# DRV8323RH.net
KiCad netlist of a schematic drawn in EAGLE
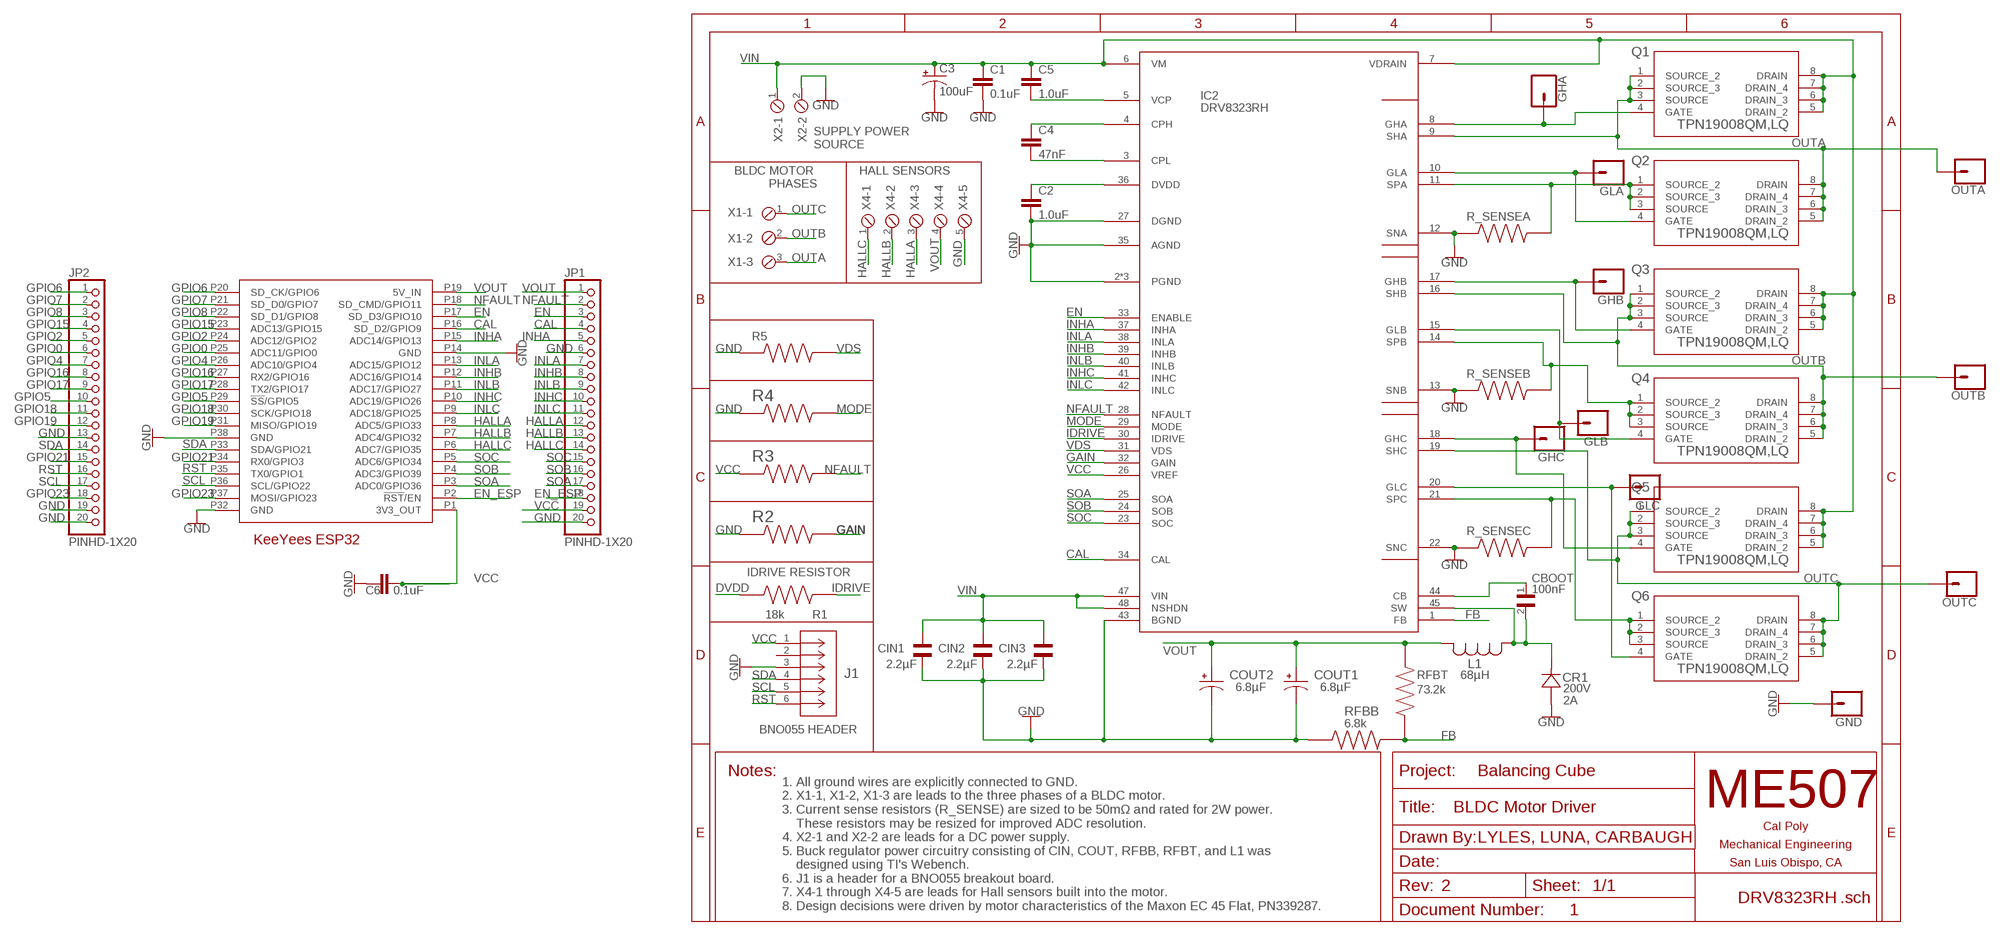
[diagram p0: schematic, sheet 1]

(export (version "E")
  (design (tool "Eeschema 10.0.6"))
  (components
    (comp (ref "C1")
      (value "0.1uF")
      (footprint "eagle-import:0603")
      (libsource (lib "eagle-import") (part "0.1UF-0603-50V-10%-X7R-WE"))
    )
    (comp (ref "C2")
      (value "1.0uF")
      (footprint "eagle-import:0805")
      (libsource (lib "eagle-import") (part "1.0UF-0805-25V-10%"))
    )
    (comp (ref "C3")
      (value "100uF")
      (footprint "eagle-import:CPOL-RADIAL-2.5MM-6.5MM")
      (libsource (lib "eagle-import") (part "100UF-POLAR-RADIAL-2.5MM-25V-20%"))
    )
    (comp (ref "C4")
      (value "47nF")
      (footprint "eagle-import:0603")
      (libsource (lib "eagle-import") (part "47NF-0603-25V-5%"))
    )
    (comp (ref "C5")
      (value "1.0uF")
      (footprint "eagle-import:0805")
      (libsource (lib "eagle-import") (part "1.0UF-0805-25V-10%"))
    )
    (comp (ref "C6")
      (value "0.1uF")
      (footprint "eagle-import:0603")
      (libsource (lib "eagle-import") (part "0.1UF-0603-50V-10%-X7R-WE"))
    )
    (comp (ref "CBOOT")
      (value "C2012X7R2A104K125AA")
      (footprint "eagle-import:CAPC2012X145N")
      (fields (field (name "MF") "TDK") (field (name "VAL") "100nF"))
      (libsource (lib "eagle-import") (part "C2012X7R2A104K125AA"))
    )
    (comp (ref "CIN1")
      (value "C3225X7R2A225K230AB")
      (footprint "eagle-import:CAP_C3225X7R2A225K230AB")
      (fields (field (name "MF") "TDK") (field (name "VAL") "2.2µF"))
      (libsource (lib "eagle-import") (part "C3225X7R2A225K230AB"))
    )
    (comp (ref "CIN2")
      (value "C3225X7R2A225K230AB")
      (footprint "eagle-import:CAP_C3225X7R2A225K230AB")
      (fields (field (name "MF") "TDK") (field (name "VAL") "2.2µF"))
      (libsource (lib "eagle-import") (part "C3225X7R2A225K230AB"))
    )
    (comp (ref "CIN3")
      (value "C3225X7R2A225K230AB")
      (footprint "eagle-import:CAP_C3225X7R2A225K230AB")
      (fields (field (name "MF") "TDK") (field (name "VAL") "2.2µF"))
      (libsource (lib "eagle-import") (part "C3225X7R2A225K230AB"))
    )
    (comp (ref "COUT1")
      (value "TPSD685K050R0600")
      (footprint "eagle-import:CAPPM7343X310N")
      (fields
        (field (name "DIGI-KEY_PART_NUMBER") "478-4121-2-ND")
        (field (name "MF") "AVX")
        (field (name "VAL") "6.8µF")
      )
      (libsource (lib "eagle-import") (part "TPSD685K050R0600"))
    )
    (comp (ref "COUT2")
      (value "TPSD685K050R0600")
      (footprint "eagle-import:CAPPM7343X310N")
      (fields
        (field (name "DIGI-KEY_PART_NUMBER") "478-4121-2-ND")
        (field (name "MF") "AVX")
        (field (name "VAL") "6.8µF")
      )
      (libsource (lib "eagle-import") (part "TPSD685K050R0600"))
    )
    (comp (ref "CR1")
      (value "SK220ATRDIODE_SK220ATR_SMC-L")
      (footprint "eagle-import:DIODE_SK220ATR_SMC-L")
      (fields
        (field (name "MANUFACTURER_PART_NUMBER") "SK220ATR")
        (field (name "CURR") "2A")
        (field (name "VOLT") "200V")
        (field (name "COPYRIGHT") "Copyright (C) 2022 Ultra Librarian. All rights reserved.")
      )
      (libsource (lib "eagle-import") (part "SK220ATRDIODE_SK220ATR_SMC-L"))
    )
    (comp (ref "GHA")
      (value "CONN_01_1MM")
      (footprint "eagle-import:1X01_1MM_NO_SILK")
      (libsource (lib "eagle-import") (part "CONN_01_1MM"))
    )
    (comp (ref "GHB")
      (value "CONN_01_1MM")
      (footprint "eagle-import:1X01_1MM_NO_SILK")
      (libsource (lib "eagle-import") (part "CONN_01_1MM"))
    )
    (comp (ref "GHC")
      (value "CONN_01_1MM")
      (footprint "eagle-import:1X01_1MM_NO_SILK")
      (libsource (lib "eagle-import") (part "CONN_01_1MM"))
    )
    (comp (ref "GLA")
      (value "CONN_01_1MM")
      (footprint "eagle-import:1X01_1MM_NO_SILK")
      (libsource (lib "eagle-import") (part "CONN_01_1MM"))
    )
    (comp (ref "GLB")
      (value "CONN_01_1MM")
      (footprint "eagle-import:1X01_1MM_NO_SILK")
      (libsource (lib "eagle-import") (part "CONN_01_1MM"))
    )
    (comp (ref "GLC")
      (value "CONN_01_1MM")
      (footprint "eagle-import:1X01_1MM_NO_SILK")
      (libsource (lib "eagle-import") (part "CONN_01_1MM"))
    )
    (comp (ref "GND")
      (value "CONN_01_1MM")
      (footprint "eagle-import:1X01_1MM_NO_SILK")
      (libsource (lib "eagle-import") (part "CONN_01_1MM"))
    )
    (comp (ref "IC2")
      (value "DRV8323RH")
      (footprint "eagle-import:QFN50P700X700X100-49T515")
      (libsource (lib "eagle-import") (part "DRV8323RH"))
    )
    (comp (ref "J1")
      (value "PPTC061LFBN-RCCONN6_061LFBN-RC_SUL")
      (footprint "eagle-import:CONN6_061LFBN-RC_SUL")
      (fields
        (field (name "MANUFACTURER_PART_NUMBER") "PPTC061LFBN-RC")
        (field (name "COPYRIGHT") "Copyright (C) 2022 Ultra Librarian. All rights reserved.")
      )
      (libsource (lib "eagle-import") (part "PPTC061LFBN-RCCONN6_061LFBN-RC_SUL"))
    )
    (comp (ref "JP1")
      (value "PINHD-1X20")
      (footprint "eagle-import:1X20")
      (libsource (lib "eagle-import") (part "PINHD-1X20"))
    )
    (comp (ref "JP2")
      (value "PINHD-1X20")
      (footprint "eagle-import:1X20")
      (libsource (lib "eagle-import") (part "PINHD-1X20"))
    )
    (comp (ref "L1")
      (value "SRR1210-680MIND_BOURNS_SRR1210")
      (footprint "eagle-import:IND_BOURNS_SRR1210")
      (fields
        (field (name "MANUFACTURER_PART_NUMBER") "SRR1210-680M")
        (field (name "VAL") "68µH")
        (field (name "COPYRIGHT") "Copyright (C) 2022 Ultra Librarian. All rights reserved.")
      )
      (libsource (lib "eagle-import") (part "SRR1210-680MIND_BOURNS_SRR1210"))
    )
    (comp (ref "OUTA")
      (value "CONN_01_1MM")
      (footprint "eagle-import:1X01_1MM_NO_SILK")
      (libsource (lib "eagle-import") (part "CONN_01_1MM"))
    )
    (comp (ref "OUTB")
      (value "CONN_01_1MM")
      (footprint "eagle-import:1X01_1MM_NO_SILK")
      (libsource (lib "eagle-import") (part "CONN_01_1MM"))
    )
    (comp (ref "OUTC")
      (value "CONN_01_1MM")
      (footprint "eagle-import:1X01_1MM_NO_SILK")
      (libsource (lib "eagle-import") (part "CONN_01_1MM"))
    )
    (comp (ref "Q1")
      (value "TPN19008QM,LQ")
      (footprint "eagle-import:TSON_ADVANCE_TOS")
      (fields (field (name "COPYRIGHT") "Copyright (C) 2022 Ultra Librarian. All rights reserved."))
      (libsource (lib "eagle-import") (part "TPN19008QM,LQ"))
    )
    (comp (ref "Q2")
      (value "TPN19008QM,LQ")
      (footprint "eagle-import:TSON_ADVANCE_TOS")
      (fields (field (name "COPYRIGHT") "Copyright (C) 2022 Ultra Librarian. All rights reserved."))
      (libsource (lib "eagle-import") (part "TPN19008QM,LQ"))
    )
    (comp (ref "Q3")
      (value "TPN19008QM,LQ")
      (footprint "eagle-import:TSON_ADVANCE_TOS")
      (fields (field (name "COPYRIGHT") "Copyright (C) 2022 Ultra Librarian. All rights reserved."))
      (libsource (lib "eagle-import") (part "TPN19008QM,LQ"))
    )
    (comp (ref "Q4")
      (value "TPN19008QM,LQ")
      (footprint "eagle-import:TSON_ADVANCE_TOS")
      (fields (field (name "COPYRIGHT") "Copyright (C) 2022 Ultra Librarian. All rights reserved."))
      (libsource (lib "eagle-import") (part "TPN19008QM,LQ"))
    )
    (comp (ref "Q5")
      (value "TPN19008QM,LQ")
      (footprint "eagle-import:TSON_ADVANCE_TOS")
      (fields (field (name "COPYRIGHT") "Copyright (C) 2022 Ultra Librarian. All rights reserved."))
      (libsource (lib "eagle-import") (part "TPN19008QM,LQ"))
    )
    (comp (ref "Q6")
      (value "TPN19008QM,LQ")
      (footprint "eagle-import:TSON_ADVANCE_TOS")
      (fields (field (name "COPYRIGHT") "Copyright (C) 2022 Ultra Librarian. All rights reserved."))
      (libsource (lib "eagle-import") (part "TPN19008QM,LQ"))
    )
    (comp (ref "R1")
      (value "ERJP06J183V")
      (footprint "eagle-import:RES_ERJP06J183V")
      (fields
        (field (name "DIGI-KEY_PART_NUMBER") "P18KADTR-ND")
        (field (name "MF") "Panasonic")
        (field (name "NAM") "R1")
        (field (name "VAL") "18k")
      )
      (libsource (lib "eagle-import") (part "ERJP06J183V"))
    )
    (comp (ref "R2")
      (value "RMCF0805JT750K")
      (footprint "eagle-import:RESC2012X65N")
      (fields
        (field (name "DIGI-KEY_PART_NUMBER") "RMCF0805JT750KTR-ND")
        (field (name "MF") "Stackpole Electronics Inc")
      )
      (libsource (lib "eagle-import") (part "RMCF0805JT750K"))
    )
    (comp (ref "R3")
      (value "RC0805JR-0710KP")
      (footprint "eagle-import:RESC2012X60N")
      (fields (field (name "DIGI-KEY_PART_NUMBER") "YAG1329TR-ND") (field (name "MF") "Yageo"))
      (libsource (lib "eagle-import") (part "RC0805JR-0710KP"))
    )
    (comp (ref "R4")
      (value "RNCF0805DTE47K0")
      (footprint "eagle-import:RESC2012X65N")
      (fields
        (field (name "DIGI-KEY_PART_NUMBER") "738-RNCF0805DTE47K0TR-ND")
        (field (name "MF") "Stackpole Electronics Inc")
      )
      (libsource (lib "eagle-import") (part "RNCF0805DTE47K0"))
    )
    (comp (ref "R5")
      (value "ERJP06J183V")
      (footprint "eagle-import:RES_ERJP06J183V")
      (fields (field (name "DIGI-KEY_PART_NUMBER") "P18KADTR-ND") (field (name "MF") "Panasonic"))
      (libsource (lib "eagle-import") (part "ERJP06J183V"))
    )
    (comp (ref "RFBB")
      (value "RC1206FR-076K8L")
      (footprint "eagle-import:RESC3116X65N")
      (fields
        (field (name "DIGI-KEY_PART_NUMBER") "311-6.80KFRTR-ND")
        (field (name "MF") "Yageo")
        (field (name "VAL") "6.8k")
      )
      (libsource (lib "eagle-import") (part "RC1206FR-076K8L"))
    )
    (comp (ref "RFBT")
      (value "RR1220P-7322-D-M")
      (footprint "eagle-import:RESC2012X50N")
      (fields
        (field (name "DIGI-KEY_PART_NUMBER") "RR12P73.2KDTR-ND")
        (field (name "MF") "Susumu")
        (field (name "VAL") "73.2k")
      )
      (libsource (lib "eagle-import") (part "RR1220P-7322-D-M"))
    )
    (comp (ref "R_SENSEA")
      (value "CRM2512-FX-R300ELF")
      (footprint "eagle-import:RESC6331X80N")
      (fields
        (field (name "DIGI-KEY_PART_NUMBER") "CRM2512-FX-R300ELFTR-ND")
        (field (name "MF") "Bourns")
        (field (name "VAL") "0.305")
      )
      (libsource (lib "eagle-import") (part "CRM2512-FX-R300ELF"))
    )
    (comp (ref "R_SENSEB")
      (value "CRM2512-FX-R300ELF")
      (footprint "eagle-import:RESC6331X80N")
      (fields (field (name "DIGI-KEY_PART_NUMBER") "CRM2512-FX-R300ELFTR-ND") (field (name "MF") "Bourns"))
      (libsource (lib "eagle-import") (part "CRM2512-FX-R300ELF"))
    )
    (comp (ref "R_SENSEC")
      (value "CRM2512-FX-R300ELF")
      (footprint "eagle-import:RESC6331X80N")
      (fields (field (name "DIGI-KEY_PART_NUMBER") "CRM2512-FX-R300ELFTR-ND") (field (name "MF") "Bourns"))
      (libsource (lib "eagle-import") (part "CRM2512-FX-R300ELF"))
    )
    (comp (ref "U$1")
      (value "KEEYEES_ESP32EXT")
      (footprint "eagle-import:KEEYEES_ESP32_EXTENDED")
      (libsource (lib "eagle-import") (part "KEEYEES_ESP32EXT"))
    )
    (comp (ref "X1")
      (value "SCREWTERM_3P_508")
      (footprint "eagle-import:3POL508")
      (libsource (lib "eagle-import") (part "SCREWTERM_3P_508"))
    )
    (comp (ref "X2")
      (value "SCREWTERM_2P_508")
      (footprint "eagle-import:2POL508")
      (libsource (lib "eagle-import") (part "SCREWTERM_2P_508"))
    )
    (comp (ref "X4")
      (value "SCREWTERM_5P_508")
      (footprint "eagle-import:5POL508")
      (libsource (lib "eagle-import") (part "SCREWTERM_5P_508"))
    )
  )
  (nets
    (net (code "1") (name "/CAL") (class "Default")
      (node (ref "IC2") (pin "34") (pinfunction "CAL_34") (pintype "bidirectional"))
      (node (ref "JP1") (pin "4") (pinfunction "4_4") (pintype "passive"))
      (node (ref "U$1") (pin "P16") (pinfunction "SD_D2/GPIO9_P16") (pintype "bidirectional"))
    )
    (net (code "2") (name "/DVDD") (class "Default")
      (node (ref "C2") (pin "1") (pinfunction "1_1") (pintype "passive"))
      (node (ref "IC2") (pin "36") (pinfunction "DVDD_36") (pintype "bidirectional"))
      (node (ref "R1") (pin "1") (pinfunction "1_1") (pintype "passive"))
    )
    (net (code "3") (name "/EN") (class "Default")
      (node (ref "IC2") (pin "33") (pinfunction "ENABLE_33") (pintype "bidirectional"))
      (node (ref "JP1") (pin "3") (pinfunction "3_3") (pintype "passive"))
      (node (ref "U$1") (pin "P17") (pinfunction "SD_D3/GPIO10_P17") (pintype "bidirectional"))
    )
    (net (code "4") (name "/EN_ESP") (class "Default")
      (node (ref "JP1") (pin "18") (pinfunction "18_18") (pintype "passive"))
      (node (ref "U$1") (pin "P2") (pinfunction "~{RST}/EN_P2") (pintype "input"))
    )
    (net (code "5") (name "/FB") (class "Default")
      (node (ref "IC2") (pin "1") (pinfunction "FB_1") (pintype "bidirectional"))
      (node (ref "RFBB") (pin "2") (pinfunction "2_2") (pintype "passive"))
      (node (ref "RFBT") (pin "1") (pinfunction "1_1") (pintype "passive"))
    )
    (net (code "6") (name "/GAIN") (class "Default")
      (node (ref "IC2") (pin "32") (pinfunction "GAIN_32") (pintype "bidirectional"))
      (node (ref "R2") (pin "2") (pinfunction "2_2") (pintype "passive"))
    )
    (net (code "7") (name "/GPIO0") (class "Default")
      (node (ref "JP2") (pin "6") (pinfunction "6_6") (pintype "passive"))
      (node (ref "U$1") (pin "P25") (pinfunction "ADC11/GPIO0_P25") (pintype "bidirectional"))
    )
    (net (code "8") (name "/GPIO2") (class "Default")
      (node (ref "JP2") (pin "5") (pinfunction "5_5") (pintype "passive"))
      (node (ref "U$1") (pin "P24") (pinfunction "ADC12/GPIO2_P24") (pintype "bidirectional"))
    )
    (net (code "9") (name "/GPIO4") (class "Default")
      (node (ref "JP2") (pin "7") (pinfunction "7_7") (pintype "passive"))
      (node (ref "U$1") (pin "P26") (pinfunction "ADC10/GPIO4_P26") (pintype "bidirectional"))
    )
    (net (code "10") (name "/GPIO5") (class "Default")
      (node (ref "JP2") (pin "10") (pinfunction "10_10") (pintype "passive"))
      (node (ref "U$1") (pin "P29") (pinfunction "~{SS}/GPIO5_P29") (pintype "bidirectional"))
    )
    (net (code "11") (name "/GPIO6") (class "Default")
      (node (ref "JP2") (pin "1") (pinfunction "1_1") (pintype "passive"))
      (node (ref "U$1") (pin "P20") (pinfunction "SD_CK/GPIO6_P20") (pintype "bidirectional"))
    )
    (net (code "12") (name "/GPIO7") (class "Default")
      (node (ref "JP2") (pin "2") (pinfunction "2_2") (pintype "passive"))
      (node (ref "U$1") (pin "P21") (pinfunction "SD_D0/GPIO7_P21") (pintype "bidirectional"))
    )
    (net (code "13") (name "/GPIO8") (class "Default")
      (node (ref "JP2") (pin "3") (pinfunction "3_3") (pintype "passive"))
      (node (ref "U$1") (pin "P22") (pinfunction "SD_D1/GPIO8_P22") (pintype "bidirectional"))
    )
    (net (code "14") (name "/GPIO15") (class "Default")
      (node (ref "JP2") (pin "4") (pinfunction "4_4") (pintype "passive"))
      (node (ref "U$1") (pin "P23") (pinfunction "ADC13/GPIO15_P23") (pintype "bidirectional"))
    )
    (net (code "15") (name "/GPIO16") (class "Default")
      (node (ref "JP2") (pin "8") (pinfunction "8_8") (pintype "passive"))
      (node (ref "U$1") (pin "P27") (pinfunction "RX2/GPIO16_P27") (pintype "bidirectional"))
    )
    (net (code "16") (name "/GPIO17") (class "Default")
      (node (ref "JP2") (pin "9") (pinfunction "9_9") (pintype "passive"))
      (node (ref "U$1") (pin "P28") (pinfunction "TX2/GPIO17_P28") (pintype "bidirectional"))
    )
    (net (code "17") (name "/GPIO18") (class "Default")
      (node (ref "JP2") (pin "11") (pinfunction "11_11") (pintype "passive"))
      (node (ref "U$1") (pin "P30") (pinfunction "SCK/GPIO18_P30") (pintype "bidirectional"))
    )
    (net (code "18") (name "/GPIO19") (class "Default")
      (node (ref "JP2") (pin "12") (pinfunction "12_12") (pintype "passive"))
      (node (ref "U$1") (pin "P31") (pinfunction "MISO/GPIO19_P31") (pintype "bidirectional"))
    )
    (net (code "19") (name "/GPIO21") (class "Default")
      (node (ref "JP2") (pin "15") (pinfunction "15_15") (pintype "passive"))
      (node (ref "U$1") (pin "P34") (pinfunction "RX0/GPIO3_P34") (pintype "bidirectional"))
    )
    (net (code "20") (name "/GPIO23") (class "Default")
      (node (ref "JP2") (pin "18") (pinfunction "18_18") (pintype "passive"))
      (node (ref "U$1") (pin "P37") (pinfunction "MOSI/GPIO23_P37") (pintype "bidirectional"))
    )
    (net (code "21") (name "/HALLA") (class "Default")
      (node (ref "JP1") (pin "12") (pinfunction "12_12") (pintype "passive"))
      (node (ref "U$1") (pin "P8") (pinfunction "ADC5/GPIO33_P8") (pintype "bidirectional"))
      (node (ref "X4") (pin "3") (pinfunction "1_3") (pintype "passive"))
    )
    (net (code "22") (name "/HALLB") (class "Default")
      (node (ref "JP1") (pin "13") (pinfunction "13_13") (pintype "passive"))
      (node (ref "U$1") (pin "P7") (pinfunction "ADC4/GPIO32_P7") (pintype "bidirectional"))
      (node (ref "X4") (pin "2") (pinfunction "1_2") (pintype "passive"))
    )
    (net (code "23") (name "/HALLC") (class "Default")
      (node (ref "JP1") (pin "14") (pinfunction "14_14") (pintype "passive"))
      (node (ref "U$1") (pin "P6") (pinfunction "ADC7/GPIO35_P6") (pintype "bidirectional"))
      (node (ref "X4") (pin "1") (pinfunction "1_1") (pintype "passive"))
    )
    (net (code "24") (name "/IDRIVE") (class "Default")
      (node (ref "IC2") (pin "30") (pinfunction "IDRIVE_30") (pintype "bidirectional"))
      (node (ref "R1") (pin "2") (pinfunction "2_2") (pintype "passive"))
    )
    (net (code "25") (name "/INHA") (class "Default")
      (node (ref "IC2") (pin "37") (pinfunction "INHA_37") (pintype "bidirectional"))
      (node (ref "JP1") (pin "5") (pinfunction "5_5") (pintype "passive"))
      (node (ref "U$1") (pin "P15") (pinfunction "ADC14/GPIO13_P15") (pintype "bidirectional"))
    )
    (net (code "26") (name "/INHB") (class "Default")
      (node (ref "IC2") (pin "39") (pinfunction "INHB_39") (pintype "bidirectional"))
      (node (ref "JP1") (pin "8") (pinfunction "8_8") (pintype "passive"))
      (node (ref "U$1") (pin "P12") (pinfunction "ADC16/GPIO14_P12") (pintype "bidirectional"))
    )
    (net (code "27") (name "/INHC") (class "Default")
      (node (ref "IC2") (pin "41") (pinfunction "INHC_41") (pintype "bidirectional"))
      (node (ref "JP1") (pin "10") (pinfunction "10_10") (pintype "passive"))
      (node (ref "U$1") (pin "P10") (pinfunction "ADC19/GPIO26_P10") (pintype "bidirectional"))
    )
    (net (code "28") (name "/INLA") (class "Default")
      (node (ref "IC2") (pin "38") (pinfunction "INLA_38") (pintype "bidirectional"))
      (node (ref "JP1") (pin "7") (pinfunction "7_7") (pintype "passive"))
      (node (ref "U$1") (pin "P13") (pinfunction "ADC15/GPIO12_P13") (pintype "bidirectional"))
    )
    (net (code "29") (name "/INLB") (class "Default")
      (node (ref "IC2") (pin "40") (pinfunction "INLB_40") (pintype "bidirectional"))
      (node (ref "JP1") (pin "9") (pinfunction "9_9") (pintype "passive"))
      (node (ref "U$1") (pin "P11") (pinfunction "ADC17/GPIO27_P11") (pintype "bidirectional"))
    )
    (net (code "30") (name "/INLC") (class "Default")
      (node (ref "IC2") (pin "42") (pinfunction "INLC_42") (pintype "bidirectional"))
      (node (ref "JP1") (pin "11") (pinfunction "11_11") (pintype "passive"))
      (node (ref "U$1") (pin "P9") (pinfunction "ADC18/GPIO25_P9") (pintype "bidirectional"))
    )
    (net (code "31") (name "/MODE") (class "Default")
      (node (ref "IC2") (pin "29") (pinfunction "MODE_29") (pintype "bidirectional"))
      (node (ref "R4") (pin "2") (pinfunction "2_2") (pintype "passive"))
    )
    (net (code "32") (name "/NFAULT") (class "Default")
      (node (ref "IC2") (pin "28") (pinfunction "NFAULT_28") (pintype "bidirectional"))
      (node (ref "JP1") (pin "2") (pinfunction "2_2") (pintype "passive"))
      (node (ref "R3") (pin "2") (pinfunction "2_2") (pintype "passive"))
      (node (ref "U$1") (pin "P18") (pinfunction "SD_CMD/GPIO11_P18") (pintype "bidirectional"))
    )
    (net (code "33") (name "/OUTA") (class "Default")
      (node (ref "IC2") (pin "9") (pinfunction "SHA_9") (pintype "bidirectional"))
      (node (ref "OUTA") (pin "1") (pinfunction "1_1") (pintype "passive"))
      (node (ref "Q1") (pin "1") (pinfunction "SOURCE_2_1") (pintype "passive"))
      (node (ref "Q1") (pin "2") (pinfunction "SOURCE_3_2") (pintype "passive"))
      (node (ref "Q1") (pin "3") (pinfunction "SOURCE_3") (pintype "passive"))
      (node (ref "Q2") (pin "5") (pinfunction "DRAIN_2_5") (pintype "passive"))
      (node (ref "Q2") (pin "6") (pinfunction "DRAIN_3_6") (pintype "passive"))
      (node (ref "Q2") (pin "7") (pinfunction "DRAIN_4_7") (pintype "passive"))
      (node (ref "Q2") (pin "8") (pinfunction "DRAIN_8") (pintype "passive"))
      (node (ref "X1") (pin "3") (pinfunction "1_3") (pintype "passive"))
    )
    (net (code "34") (name "/OUTB") (class "Default")
      (node (ref "IC2") (pin "16") (pinfunction "SHB_16") (pintype "bidirectional"))
      (node (ref "OUTB") (pin "1") (pinfunction "1_1") (pintype "passive"))
      (node (ref "Q3") (pin "1") (pinfunction "SOURCE_2_1") (pintype "passive"))
      (node (ref "Q3") (pin "2") (pinfunction "SOURCE_3_2") (pintype "passive"))
      (node (ref "Q3") (pin "3") (pinfunction "SOURCE_3") (pintype "passive"))
      (node (ref "Q4") (pin "5") (pinfunction "DRAIN_2_5") (pintype "passive"))
      (node (ref "Q4") (pin "6") (pinfunction "DRAIN_3_6") (pintype "passive"))
      (node (ref "Q4") (pin "7") (pinfunction "DRAIN_4_7") (pintype "passive"))
      (node (ref "Q4") (pin "8") (pinfunction "DRAIN_8") (pintype "passive"))
      (node (ref "X1") (pin "2") (pinfunction "1_2") (pintype "passive"))
    )
    (net (code "35") (name "/OUTC") (class "Default")
      (node (ref "IC2") (pin "19") (pinfunction "SHC_19") (pintype "bidirectional"))
      (node (ref "OUTC") (pin "1") (pinfunction "1_1") (pintype "passive"))
      (node (ref "Q5") (pin "1") (pinfunction "SOURCE_2_1") (pintype "passive"))
      (node (ref "Q5") (pin "2") (pinfunction "SOURCE_3_2") (pintype "passive"))
      (node (ref "Q5") (pin "3") (pinfunction "SOURCE_3") (pintype "passive"))
      (node (ref "Q6") (pin "5") (pinfunction "DRAIN_2_5") (pintype "passive"))
      (node (ref "Q6") (pin "6") (pinfunction "DRAIN_3_6") (pintype "passive"))
      (node (ref "Q6") (pin "7") (pinfunction "DRAIN_4_7") (pintype "passive"))
      (node (ref "Q6") (pin "8") (pinfunction "DRAIN_8") (pintype "passive"))
      (node (ref "X1") (pin "1") (pinfunction "1_1") (pintype "passive"))
    )
    (net (code "36") (name "/RST") (class "Default")
      (node (ref "J1") (pin "6") (pinfunction "6_6") (pintype "passive"))
      (node (ref "JP2") (pin "16") (pinfunction "16_16") (pintype "passive"))
      (node (ref "U$1") (pin "P35") (pinfunction "TX0/GPIO1_P35") (pintype "bidirectional"))
    )
    (net (code "37") (name "/SCL") (class "Default")
      (node (ref "J1") (pin "5") (pinfunction "5_5") (pintype "passive"))
      (node (ref "JP2") (pin "17") (pinfunction "17_17") (pintype "passive"))
      (node (ref "U$1") (pin "P36") (pinfunction "SCL/GPIO22_P36") (pintype "bidirectional"))
    )
    (net (code "38") (name "/SDA") (class "Default")
      (node (ref "J1") (pin "4") (pinfunction "4_4") (pintype "passive"))
      (node (ref "JP2") (pin "14") (pinfunction "14_14") (pintype "passive"))
      (node (ref "U$1") (pin "P33") (pinfunction "SDA/GPIO21_P33") (pintype "bidirectional"))
    )
    (net (code "39") (name "/SOA") (class "Default")
      (node (ref "IC2") (pin "25") (pinfunction "SOA_25") (pintype "bidirectional"))
      (node (ref "JP1") (pin "17") (pinfunction "17_17") (pintype "passive"))
      (node (ref "U$1") (pin "P3") (pinfunction "ADC0/GPIO36_P3") (pintype "bidirectional"))
    )
    (net (code "40") (name "/SOB") (class "Default")
      (node (ref "IC2") (pin "24") (pinfunction "SOB_24") (pintype "bidirectional"))
      (node (ref "JP1") (pin "16") (pinfunction "16_16") (pintype "passive"))
      (node (ref "U$1") (pin "P4") (pinfunction "ADC3/GPIO39_P4") (pintype "bidirectional"))
    )
    (net (code "41") (name "/SOC") (class "Default")
      (node (ref "IC2") (pin "23") (pinfunction "SOC_23") (pintype "bidirectional"))
      (node (ref "JP1") (pin "15") (pinfunction "15_15") (pintype "passive"))
      (node (ref "U$1") (pin "P5") (pinfunction "ADC6/GPIO34_P5") (pintype "bidirectional"))
    )
    (net (code "42") (name "/VCC") (class "Default")
      (node (ref "C6") (pin "1") (pinfunction "1_1") (pintype "passive"))
      (node (ref "IC2") (pin "26") (pinfunction "VREF_26") (pintype "bidirectional"))
      (node (ref "J1") (pin "1") (pinfunction "1_1") (pintype "passive"))
      (node (ref "JP1") (pin "19") (pinfunction "19_19") (pintype "passive"))
      (node (ref "R3") (pin "1") (pinfunction "1_1") (pintype "passive"))
      (node (ref "U$1") (pin "P1") (pinfunction "3V3_OUT_P1") (pintype "power_in"))
    )
    (net (code "43") (name "/VDS") (class "Default")
      (node (ref "IC2") (pin "31") (pinfunction "VDS_31") (pintype "bidirectional"))
      (node (ref "R5") (pin "2") (pinfunction "2_2") (pintype "passive"))
    )
    (net (code "44") (name "/VIN") (class "Default")
      (node (ref "C1") (pin "1") (pinfunction "1_1") (pintype "passive"))
      (node (ref "C3") (pin "1") (pinfunction "+_1") (pintype "passive"))
      (node (ref "C5") (pin "1") (pinfunction "1_1") (pintype "passive"))
      (node (ref "CIN1") (pin "2") (pinfunction "2_2") (pintype "passive"))
      (node (ref "CIN2") (pin "2") (pinfunction "2_2") (pintype "passive"))
      (node (ref "CIN3") (pin "2") (pinfunction "2_2") (pintype "passive"))
      (node (ref "IC2") (pin "47") (pinfunction "VIN_47") (pintype "bidirectional"))
      (node (ref "IC2") (pin "48") (pinfunction "NSHDN_48") (pintype "bidirectional"))
      (node (ref "IC2") (pin "6") (pinfunction "VM_6") (pintype "bidirectional"))
      (node (ref "IC2") (pin "7") (pinfunction "VDRAIN_7") (pintype "bidirectional"))
      (node (ref "Q1") (pin "5") (pinfunction "DRAIN_2_5") (pintype "passive"))
      (node (ref "Q1") (pin "6") (pinfunction "DRAIN_3_6") (pintype "passive"))
      (node (ref "Q1") (pin "7") (pinfunction "DRAIN_4_7") (pintype "passive"))
      (node (ref "Q1") (pin "8") (pinfunction "DRAIN_8") (pintype "passive"))
      (node (ref "Q3") (pin "5") (pinfunction "DRAIN_2_5") (pintype "passive"))
      (node (ref "Q3") (pin "6") (pinfunction "DRAIN_3_6") (pintype "passive"))
      (node (ref "Q3") (pin "7") (pinfunction "DRAIN_4_7") (pintype "passive"))
      (node (ref "Q3") (pin "8") (pinfunction "DRAIN_8") (pintype "passive"))
      (node (ref "Q5") (pin "5") (pinfunction "DRAIN_2_5") (pintype "passive"))
      (node (ref "Q5") (pin "6") (pinfunction "DRAIN_3_6") (pintype "passive"))
      (node (ref "Q5") (pin "7") (pinfunction "DRAIN_4_7") (pintype "passive"))
      (node (ref "Q5") (pin "8") (pinfunction "DRAIN_8") (pintype "passive"))
      (node (ref "X2") (pin "1") (pinfunction "1_1") (pintype "passive"))
    )
    (net (code "45") (name "/VOUT") (class "Default")
      (node (ref "COUT1") (pin "1") (pinfunction "1_1") (pintype "passive"))
      (node (ref "COUT2") (pin "1") (pinfunction "1_1") (pintype "passive"))
      (node (ref "JP1") (pin "1") (pinfunction "1_1") (pintype "passive"))
      (node (ref "L1") (pin "1") (pinfunction "1_1") (pintype "passive"))
      (node (ref "RFBT") (pin "2") (pinfunction "2_2") (pintype "passive"))
      (node (ref "U$1") (pin "P19") (pinfunction "5V_IN_P19") (pintype "power_in"))
      (node (ref "X4") (pin "4") (pinfunction "1_4") (pintype "passive"))
    )
    (net (code "46") (name "GND") (class "Default")
      (node (ref "C1") (pin "2") (pinfunction "2_2") (pintype "passive"))
      (node (ref "C2") (pin "2") (pinfunction "2_2") (pintype "passive"))
      (node (ref "C3") (pin "2") (pinfunction "-_2") (pintype "passive"))
      (node (ref "C6") (pin "2") (pinfunction "2_2") (pintype "passive"))
      (node (ref "CIN1") (pin "1") (pinfunction "1_1") (pintype "passive"))
      (node (ref "CIN2") (pin "1") (pinfunction "1_1") (pintype "passive"))
      (node (ref "CIN3") (pin "1") (pinfunction "1_1") (pintype "passive"))
      (node (ref "COUT1") (pin "2") (pinfunction "2_2") (pintype "passive"))
      (node (ref "COUT2") (pin "2") (pinfunction "2_2") (pintype "passive"))
      (node (ref "CR1") (pin "2") (pinfunction "2_2") (pintype "passive"))
      (node (ref "GND") (pin "1") (pinfunction "1_1") (pintype "passive"))
      (node (ref "IC2") (pin "12") (pinfunction "SNA_12") (pintype "bidirectional"))
      (node (ref "IC2") (pin "13") (pinfunction "SNB_13") (pintype "bidirectional"))
      (node (ref "IC2") (pin "2") (pinfunction "PGND_2") (pintype "bidirectional"))
      (node (ref "IC2") (pin "22") (pinfunction "SNC_22") (pintype "bidirectional"))
      (node (ref "IC2") (pin "27") (pinfunction "DGND_27") (pintype "bidirectional"))
      (node (ref "IC2") (pin "35") (pinfunction "AGND_35") (pintype "bidirectional"))
      (node (ref "IC2") (pin "43") (pinfunction "BGND_43") (pintype "bidirectional"))
      (node (ref "IC2") (pin "46") (pinfunction "PGND_46") (pintype "bidirectional"))
      (node (ref "IC2") (pin "49") (pinfunction "PGND_49") (pintype "bidirectional"))
      (node (ref "J1") (pin "3") (pinfunction "3_3") (pintype "passive"))
      (node (ref "JP1") (pin "20") (pinfunction "20_20") (pintype "passive"))
      (node (ref "JP1") (pin "6") (pinfunction "6_6") (pintype "passive"))
      (node (ref "JP2") (pin "13") (pinfunction "13_13") (pintype "passive"))
      (node (ref "JP2") (pin "19") (pinfunction "19_19") (pintype "passive"))
      (node (ref "JP2") (pin "20") (pinfunction "20_20") (pintype "passive"))
      (node (ref "R2") (pin "1") (pinfunction "1_1") (pintype "passive"))
      (node (ref "R4") (pin "1") (pinfunction "1_1") (pintype "passive"))
      (node (ref "R5") (pin "1") (pinfunction "1_1") (pintype "passive"))
      (node (ref "RFBB") (pin "1") (pinfunction "1_1") (pintype "passive"))
      (node (ref "R_SENSEA") (pin "1") (pinfunction "1_1") (pintype "passive"))
      (node (ref "R_SENSEB") (pin "1") (pinfunction "1_1") (pintype "passive"))
      (node (ref "R_SENSEC") (pin "1") (pinfunction "1_1") (pintype "passive"))
      (node (ref "U$1") (pin "P14") (pinfunction "GND_P14") (pintype "power_in"))
      (node (ref "U$1") (pin "P32") (pinfunction "GND_P32") (pintype "power_in"))
      (node (ref "U$1") (pin "P38") (pinfunction "GND_P38") (pintype "power_in"))
      (node (ref "X2") (pin "2") (pinfunction "1_2") (pintype "passive"))
      (node (ref "X4") (pin "5") (pinfunction "1_5") (pintype "passive"))
    )
    (net (code "47") (name "Net-(IC2-CB)") (class "Default")
      (node (ref "CBOOT") (pin "1") (pinfunction "1_1") (pintype "passive"))
      (node (ref "IC2") (pin "44") (pinfunction "CB_44") (pintype "bidirectional"))
    )
    (net (code "48") (name "Net-(IC2-CPH)") (class "Default")
      (node (ref "C4") (pin "1") (pinfunction "1_1") (pintype "passive"))
      (node (ref "IC2") (pin "4") (pinfunction "CPH_4") (pintype "bidirectional"))
    )
    (net (code "49") (name "Net-(IC2-CPL)") (class "Default")
      (node (ref "C4") (pin "2") (pinfunction "2_2") (pintype "passive"))
      (node (ref "IC2") (pin "3") (pinfunction "CPL_3") (pintype "bidirectional"))
    )
    (net (code "50") (name "Net-(IC2-GHA)") (class "Default")
      (node (ref "GHA") (pin "1") (pinfunction "1_1") (pintype "passive"))
      (node (ref "IC2") (pin "8") (pinfunction "GHA_8") (pintype "bidirectional"))
      (node (ref "Q1") (pin "4") (pinfunction "GATE_4") (pintype "passive"))
    )
    (net (code "51") (name "Net-(IC2-GHB)") (class "Default")
      (node (ref "GHB") (pin "1") (pinfunction "1_1") (pintype "passive"))
      (node (ref "IC2") (pin "17") (pinfunction "GHB_17") (pintype "bidirectional"))
      (node (ref "Q3") (pin "4") (pinfunction "GATE_4") (pintype "passive"))
    )
    (net (code "52") (name "Net-(IC2-GHC)") (class "Default")
      (node (ref "GHC") (pin "1") (pinfunction "1_1") (pintype "passive"))
      (node (ref "IC2") (pin "18") (pinfunction "GHC_18") (pintype "bidirectional"))
      (node (ref "Q5") (pin "4") (pinfunction "GATE_4") (pintype "passive"))
    )
    (net (code "53") (name "Net-(IC2-GLA)") (class "Default")
      (node (ref "GLA") (pin "1") (pinfunction "1_1") (pintype "passive"))
      (node (ref "IC2") (pin "10") (pinfunction "GLA_10") (pintype "bidirectional"))
      (node (ref "Q2") (pin "4") (pinfunction "GATE_4") (pintype "passive"))
    )
    (net (code "54") (name "Net-(IC2-GLB)") (class "Default")
      (node (ref "GLB") (pin "1") (pinfunction "1_1") (pintype "passive"))
      (node (ref "IC2") (pin "15") (pinfunction "GLB_15") (pintype "bidirectional"))
      (node (ref "Q4") (pin "4") (pinfunction "GATE_4") (pintype "passive"))
    )
    (net (code "55") (name "Net-(IC2-GLC)") (class "Default")
      (node (ref "GLC") (pin "1") (pinfunction "1_1") (pintype "passive"))
      (node (ref "IC2") (pin "20") (pinfunction "GLC_20") (pintype "bidirectional"))
      (node (ref "Q6") (pin "4") (pinfunction "GATE_4") (pintype "passive"))
    )
    (net (code "56") (name "Net-(IC2-SPA)") (class "Default")
      (node (ref "IC2") (pin "11") (pinfunction "SPA_11") (pintype "bidirectional"))
      (node (ref "Q2") (pin "1") (pinfunction "SOURCE_2_1") (pintype "passive"))
      (node (ref "Q2") (pin "2") (pinfunction "SOURCE_3_2") (pintype "passive"))
      (node (ref "Q2") (pin "3") (pinfunction "SOURCE_3") (pintype "passive"))
      (node (ref "R_SENSEA") (pin "2") (pinfunction "2_2") (pintype "passive"))
    )
    (net (code "57") (name "Net-(IC2-SPB)") (class "Default")
      (node (ref "IC2") (pin "14") (pinfunction "SPB_14") (pintype "bidirectional"))
      (node (ref "Q4") (pin "1") (pinfunction "SOURCE_2_1") (pintype "passive"))
      (node (ref "Q4") (pin "2") (pinfunction "SOURCE_3_2") (pintype "passive"))
      (node (ref "Q4") (pin "3") (pinfunction "SOURCE_3") (pintype "passive"))
      (node (ref "R_SENSEB") (pin "2") (pinfunction "2_2") (pintype "passive"))
    )
    (net (code "58") (name "Net-(IC2-SPC)") (class "Default")
      (node (ref "IC2") (pin "21") (pinfunction "SPC_21") (pintype "bidirectional"))
      (node (ref "Q6") (pin "1") (pinfunction "SOURCE_2_1") (pintype "passive"))
      (node (ref "Q6") (pin "2") (pinfunction "SOURCE_3_2") (pintype "passive"))
      (node (ref "Q6") (pin "3") (pinfunction "SOURCE_3") (pintype "passive"))
      (node (ref "R_SENSEC") (pin "2") (pinfunction "2_2") (pintype "passive"))
    )
    (net (code "59") (name "Net-(IC2-SW)") (class "Default")
      (node (ref "CBOOT") (pin "2") (pinfunction "2_2") (pintype "passive"))
      (node (ref "CR1") (pin "1") (pinfunction "1_1") (pintype "passive"))
      (node (ref "IC2") (pin "45") (pinfunction "SW_45") (pintype "bidirectional"))
      (node (ref "L1") (pin "2") (pinfunction "2_2") (pintype "passive"))
    )
    (net (code "60") (name "Net-(IC2-VCP)") (class "Default")
      (node (ref "C5") (pin "2") (pinfunction "2_2") (pintype "passive"))
      (node (ref "IC2") (pin "5") (pinfunction "VCP_5") (pintype "bidirectional"))
    )
    (net (code "61") (name "unconnected-(J1-Pad2)") (class "Default")
      (node (ref "J1") (pin "2") (pinfunction "2_2") (pintype "passive"))
    )
  )
)
